# basePCB.net
KiCad netlist of a schematic drawn in EAGLE
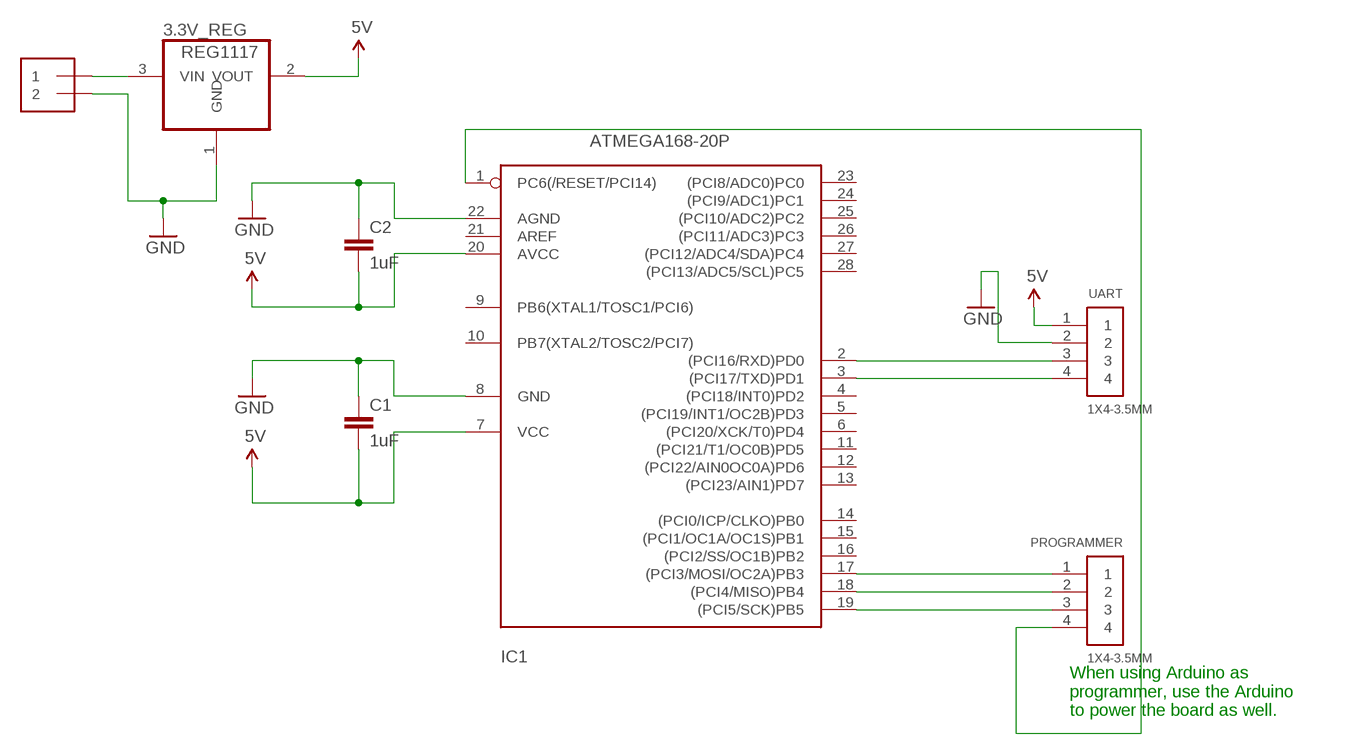
[diagram p0: schematic, sheet 1]

(export (version "E")
  (design (tool "Eeschema 10.0.6"))
  (components
    (comp (ref "3.3V_REG")
      (value "REG1117")
      (footprint "eagle-import:SOT223")
      (libsource (lib "eagle-import") (part "REG1117"))
    )
    (comp (ref "C1")
      (value "1uF")
      (footprint "eagle-import:CAP-PTH-SMALL")
      (libsource (lib "eagle-import") (part "CAPPTH"))
    )
    (comp (ref "C2")
      (value "1uF")
      (footprint "eagle-import:CAP-PTH-SMALL")
      (libsource (lib "eagle-import") (part "CAPPTH"))
    )
    (comp (ref "IC1")
      (value "ATMEGA168-20P")
      (footprint "eagle-import:DIL28-3")
      (libsource (lib "eagle-import") (part "ATMEGA168P-20"))
    )
    (comp (ref "POWER_IN")
      (value "1X2-3.5MM")
      (footprint "eagle-import:1X2-3.5MM")
      (libsource (lib "eagle-import") (part "1X2-3.5MM"))
    )
    (comp (ref "PROGRAMMER")
      (value "1X4-3.5MM")
      (footprint "eagle-import:1X04-3.5MM")
      (libsource (lib "eagle-import") (part "1X4-3.5MM"))
    )
    (comp (ref "UART")
      (value "1X4-3.5MM")
      (footprint "eagle-import:1X04-3.5MM")
      (libsource (lib "eagle-import") (part "1X4-3.5MM"))
    )
  )
  (nets
    (net (code "1") (name "5V") (class "Default")
      (node (ref "3.3V_REG") (pin "2") (pinfunction "VOUT_2") (pintype "output"))
      (node (ref "C1") (pin "2") (pinfunction "2_2") (pintype "passive"))
      (node (ref "C2") (pin "2") (pinfunction "2_2") (pintype "passive"))
      (node (ref "IC1") (pin "20") (pinfunction "AVCC_20") (pintype "bidirectional"))
      (node (ref "IC1") (pin "7") (pinfunction "VCC_7") (pintype "bidirectional"))
      (node (ref "UART") (pin "1") (pinfunction "1_1") (pintype "bidirectional"))
    )
    (net (code "2") (name "GND") (class "Default")
      (node (ref "3.3V_REG") (pin "1") (pinfunction "GND_1") (pintype "power_in"))
      (node (ref "C1") (pin "1") (pinfunction "1_1") (pintype "passive"))
      (node (ref "C2") (pin "1") (pinfunction "1_1") (pintype "passive"))
      (node (ref "IC1") (pin "22") (pinfunction "AGND_22") (pintype "bidirectional"))
      (node (ref "IC1") (pin "8") (pinfunction "GND_8") (pintype "bidirectional"))
      (node (ref "POWER_IN") (pin "2") (pinfunction "2_2") (pintype "passive"))
      (node (ref "UART") (pin "2") (pinfunction "2_2") (pintype "bidirectional"))
    )
    (net (code "3") (name "Net-(3.3V_REG-VIN)") (class "Default")
      (node (ref "3.3V_REG") (pin "3") (pinfunction "VIN_3") (pintype "input"))
      (node (ref "POWER_IN") (pin "1") (pinfunction "1_1") (pintype "passive"))
    )
    (net (code "4") (name "Net-(IC1-(PCI3{slash}MOSI{slash}OC2A)PB3)") (class "Default")
      (node (ref "IC1") (pin "17") (pinfunction "(PCI3/MOSI/OC2A)PB3_17") (pintype "bidirectional"))
      (node (ref "PROGRAMMER") (pin "1") (pinfunction "1_1") (pintype "bidirectional"))
    )
    (net (code "5") (name "Net-(IC1-(PCI4{slash}MISO)PB4)") (class "Default")
      (node (ref "IC1") (pin "18") (pinfunction "(PCI4/MISO)PB4_18") (pintype "bidirectional"))
      (node (ref "PROGRAMMER") (pin "2") (pinfunction "2_2") (pintype "bidirectional"))
    )
    (net (code "6") (name "Net-(IC1-(PCI5{slash}SCK)PB5)") (class "Default")
      (node (ref "IC1") (pin "19") (pinfunction "(PCI5/SCK)PB5_19") (pintype "bidirectional"))
      (node (ref "PROGRAMMER") (pin "3") (pinfunction "3_3") (pintype "bidirectional"))
    )
    (net (code "7") (name "Net-(IC1-(PCI16{slash}RXD)PD0)") (class "Default")
      (node (ref "IC1") (pin "2") (pinfunction "(PCI16/RXD)PD0_2") (pintype "bidirectional"))
      (node (ref "UART") (pin "3") (pinfunction "3_3") (pintype "bidirectional"))
    )
    (net (code "8") (name "Net-(IC1-(PCI17{slash}TXD)PD1)") (class "Default")
      (node (ref "IC1") (pin "3") (pinfunction "(PCI17/TXD)PD1_3") (pintype "bidirectional"))
      (node (ref "UART") (pin "4") (pinfunction "4_4") (pintype "bidirectional"))
    )
    (net (code "9") (name "Net-(IC1-PC6({slash}RESET{slash}PCI14))") (class "Default")
      (node (ref "IC1") (pin "1") (pinfunction "PC6(/RESET/PCI14)_1") (pintype "bidirectional"))
      (node (ref "PROGRAMMER") (pin "4") (pinfunction "4_4") (pintype "bidirectional"))
    )
    (net (code "10") (name "unconnected-(IC1-(PCI0{slash}ICP{slash}CLKO)PB0-Pad14)") (class "Default")
      (node (ref "IC1") (pin "14") (pinfunction "(PCI0/ICP/CLKO)PB0_14") (pintype "bidirectional"))
    )
    (net (code "11") (name "unconnected-(IC1-(PCI1{slash}OC1A{slash}OC1S)PB1-Pad15)") (class "Default")
      (node (ref "IC1") (pin "15") (pinfunction "(PCI1/OC1A/OC1S)PB1_15") (pintype "bidirectional"))
    )
    (net (code "12") (name "unconnected-(IC1-(PCI2{slash}SS{slash}OC1B)PB2-Pad16)") (class "Default")
      (node (ref "IC1") (pin "16") (pinfunction "(PCI2/SS/OC1B)PB2_16") (pintype "bidirectional"))
    )
    (net (code "13") (name "unconnected-(IC1-(PCI8{slash}ADC0)PC0-Pad23)") (class "Default")
      (node (ref "IC1") (pin "23") (pinfunction "(PCI8/ADC0)PC0_23") (pintype "bidirectional"))
    )
    (net (code "14") (name "unconnected-(IC1-(PCI9{slash}ADC1)PC1-Pad24)") (class "Default")
      (node (ref "IC1") (pin "24") (pinfunction "(PCI9/ADC1)PC1_24") (pintype "bidirectional"))
    )
    (net (code "15") (name "unconnected-(IC1-(PCI10{slash}ADC2)PC2-Pad25)") (class "Default")
      (node (ref "IC1") (pin "25") (pinfunction "(PCI10/ADC2)PC2_25") (pintype "bidirectional"))
    )
    (net (code "16") (name "unconnected-(IC1-(PCI11{slash}ADC3)PC3-Pad26)") (class "Default")
      (node (ref "IC1") (pin "26") (pinfunction "(PCI11/ADC3)PC3_26") (pintype "bidirectional"))
    )
    (net (code "17") (name "unconnected-(IC1-(PCI12{slash}ADC4{slash}SDA)PC4-Pad27)") (class "Default")
      (node (ref "IC1") (pin "27") (pinfunction "(PCI12/ADC4/SDA)PC4_27") (pintype "bidirectional"))
    )
    (net (code "18") (name "unconnected-(IC1-(PCI13{slash}ADC5{slash}SCL)PC5-Pad28)") (class "Default")
      (node (ref "IC1") (pin "28") (pinfunction "(PCI13/ADC5/SCL)PC5_28") (pintype "bidirectional"))
    )
    (net (code "19") (name "unconnected-(IC1-(PCI18{slash}INT0)PD2-Pad4)") (class "Default")
      (node (ref "IC1") (pin "4") (pinfunction "(PCI18/INT0)PD2_4") (pintype "bidirectional"))
    )
    (net (code "20") (name "unconnected-(IC1-(PCI19{slash}INT1{slash}OC2B)PD3-Pad5)") (class "Default")
      (node (ref "IC1") (pin "5") (pinfunction "(PCI19/INT1/OC2B)PD3_5") (pintype "bidirectional"))
    )
    (net (code "21") (name "unconnected-(IC1-(PCI20{slash}XCK{slash}T0)PD4-Pad6)") (class "Default")
      (node (ref "IC1") (pin "6") (pinfunction "(PCI20/XCK/T0)PD4_6") (pintype "bidirectional"))
    )
    (net (code "22") (name "unconnected-(IC1-(PCI21{slash}T1{slash}OC0B)PD5-Pad11)") (class "Default")
      (node (ref "IC1") (pin "11") (pinfunction "(PCI21/T1/OC0B)PD5_11") (pintype "bidirectional"))
    )
    (net (code "23") (name "unconnected-(IC1-(PCI22{slash}AIN0OC0A)PD6-Pad12)") (class "Default")
      (node (ref "IC1") (pin "12") (pinfunction "(PCI22/AIN0OC0A)PD6_12") (pintype "bidirectional"))
    )
    (net (code "24") (name "unconnected-(IC1-(PCI23{slash}AIN1)PD7-Pad13)") (class "Default")
      (node (ref "IC1") (pin "13") (pinfunction "(PCI23/AIN1)PD7_13") (pintype "bidirectional"))
    )
    (net (code "25") (name "unconnected-(IC1-AREF-Pad21)") (class "Default")
      (node (ref "IC1") (pin "21") (pinfunction "AREF_21") (pintype "bidirectional"))
    )
    (net (code "26") (name "unconnected-(IC1-PB6(XTAL1{slash}TOSC1{slash}PCI6)-Pad9)") (class "Default")
      (node (ref "IC1") (pin "9") (pinfunction "PB6(XTAL1/TOSC1/PCI6)_9") (pintype "bidirectional"))
    )
    (net (code "27") (name "unconnected-(IC1-PB7(XTAL2{slash}TOSC2{slash}PCI7)-Pad10)") (class "Default")
      (node (ref "IC1") (pin "10") (pinfunction "PB7(XTAL2/TOSC2/PCI7)_10") (pintype "bidirectional"))
    )
  )
)
